# 3V3.net
KiCad netlist of a schematic drawn in Altium Designer
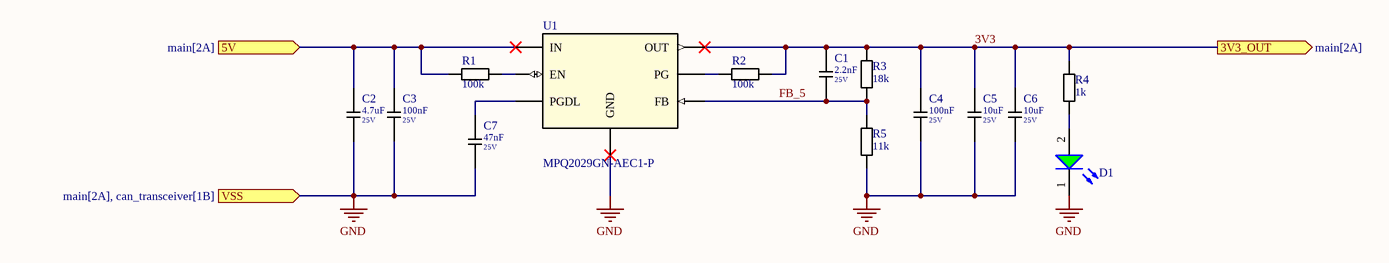
[diagram p0: 3V3.SchDoc]

(export (version "E")
  (design (tool "Eeschema 10.0.6"))
  (components
    (comp (ref "C1")
      (value "2.2nF")
      (footprint "0603_C")
      (description "Keramikkondensatoren 0603")
      (fields (field (name "SPG") "25V") (field (name "Comment") "2.2nF_25V"))
      (libsource (lib "Allgemeine_ETI_Schematic_Lib") (part "C_0603_Keramik"))
    )
    (comp (ref "C2")
      (value "4.7uF")
      (footprint "0603_C")
      (description "Keramikkondensatoren 0603")
      (fields (field (name "SPG") "25V") (field (name "Comment") "4.7uF_25V"))
      (libsource (lib "Allgemeine_ETI_Schematic_Lib") (part "C_0603_Keramik"))
    )
    (comp (ref "C3")
      (value "100nF")
      (footprint "0603_C")
      (description "Keramikkondensatoren 0603")
      (fields (field (name "SPG") "25V") (field (name "Comment") "100nF_25V"))
      (libsource (lib "Allgemeine_ETI_Schematic_Lib") (part "C_0603_Keramik"))
    )
    (comp (ref "C4")
      (value "100nF")
      (footprint "0603_C")
      (description "Keramikkondensatoren 0603")
      (fields (field (name "SPG") "25V") (field (name "Comment") "100nF_25V"))
      (libsource (lib "Allgemeine_ETI_Schematic_Lib") (part "C_0603_Keramik"))
    )
    (comp (ref "C5")
      (value "10uF")
      (footprint "0603_C")
      (description "Keramikkondensatoren 0603")
      (fields (field (name "SPG") "25V") (field (name "Comment") "10uF_25V"))
      (libsource (lib "Allgemeine_ETI_Schematic_Lib") (part "C_0603_Keramik"))
    )
    (comp (ref "C6")
      (value "10uF")
      (footprint "0603_C")
      (description "Keramikkondensatoren 0603")
      (fields (field (name "SPG") "25V") (field (name "Comment") "10uF_25V"))
      (libsource (lib "Allgemeine_ETI_Schematic_Lib") (part "C_0603_Keramik"))
    )
    (comp (ref "C7")
      (value "47nF")
      (footprint "0603_C")
      (description "Keramikkondensatoren 0603")
      (fields (field (name "SPG") "25V") (field (name "Comment") "47nF_25V"))
      (libsource (lib "Allgemeine_ETI_Schematic_Lib") (part "C_0603_Keramik"))
    )
    (comp (ref "D1")
      (value "Green, 3.2V, 140°")
      (footprint "WL-SMCD_0603")
      (description "WL-SMCD Mono-color Chip LED Diffused, SMT, size 0603, Green, 3.2V, 140°")
      (fields
        (field (name "MANUFACTURER PART NUMBER") "150060GS55040")
        (field (name "MANUFACTURER") "Wurth Elektronik")
      )
      (libsource (lib "Altium_WL-SMCD (rev24a)") (part "150060GS55040"))
    )
    (comp (ref "R1")
      (value "100k")
      (footprint "0603_R")
      (description "R 0603, 75V, 0.1W")
      (libsource (lib "Allgemeine_ETI_Schematic_Lib") (part "R_0603"))
    )
    (comp (ref "R2")
      (value "100k")
      (footprint "0603_R")
      (description "R 0603, 75V, 0.1W")
      (libsource (lib "Allgemeine_ETI_Schematic_Lib") (part "R_0603"))
    )
    (comp (ref "R3")
      (value "18k")
      (footprint "0603_R")
      (description "R 0603, 75V, 0.1W")
      (libsource (lib "") (part "R_0603_1"))
    )
    (comp (ref "R4")
      (value "1k")
      (footprint "0603_R")
      (description "R 0603, 75V, 0.1W")
      (libsource (lib "") (part "R_0603_1"))
    )
    (comp (ref "R5")
      (value "11k")
      (footprint "0603_R")
      (description "R 0603, 75V, 0.1W")
      (libsource (lib "") (part "R_0603_1"))
    )
    (comp (ref "U1")
      (value "MPQ2029GN-AEC1-P")
      (footprint "SOIC8-EP_MPQ2029_MNP")
      (description "No Description Available")
      (libsource (lib "KARaceIng25") (part "MPQ2029GN-AEC1-P"))
    )
  )
  (nets
    (net (code "1") (name "/3V3") (class "Default")
      (node (ref "C1") (pin "1") (pinfunction "1_1") (pintype "passive"))
      (node (ref "C4") (pin "1") (pinfunction "1_1") (pintype "passive"))
      (node (ref "C5") (pin "1") (pinfunction "1_1") (pintype "passive"))
      (node (ref "C6") (pin "1") (pinfunction "1_1") (pintype "passive"))
      (node (ref "R2") (pin "2") (pinfunction "2_2") (pintype "passive"))
      (node (ref "R3") (pin "2") (pinfunction "2_2") (pintype "passive"))
      (node (ref "R4") (pin "2") (pinfunction "2_2") (pintype "passive"))
      (node (ref "U1") (pin "1") (pinfunction "OUT_1") (pintype "output"))
    )
    (net (code "2") (name "/5V") (class "Default")
      (node (ref "C2") (pin "1") (pinfunction "1_1") (pintype "passive"))
      (node (ref "C3") (pin "1") (pinfunction "1_1") (pintype "passive"))
      (node (ref "R1") (pin "1") (pinfunction "1_1") (pintype "passive"))
      (node (ref "U1") (pin "4") (pinfunction "IN_4") (pintype "power_in"))
    )
    (net (code "3") (name "/FB_5") (class "Default")
      (node (ref "C1") (pin "2") (pinfunction "2_2") (pintype "passive"))
      (node (ref "R3") (pin "1") (pinfunction "1_1") (pintype "passive"))
      (node (ref "R5") (pin "2") (pinfunction "2_2") (pintype "passive"))
      (node (ref "U1") (pin "8") (pinfunction "FB_8") (pintype "input"))
    )
    (net (code "4") (name "GND") (class "Default")
      (node (ref "C2") (pin "2") (pinfunction "2_2") (pintype "passive"))
      (node (ref "C3") (pin "2") (pinfunction "2_2") (pintype "passive"))
      (node (ref "C4") (pin "2") (pinfunction "2_2") (pintype "passive"))
      (node (ref "C5") (pin "2") (pinfunction "2_2") (pintype "passive"))
      (node (ref "C6") (pin "2") (pinfunction "2_2") (pintype "passive"))
      (node (ref "C7") (pin "2") (pinfunction "2_2") (pintype "passive"))
      (node (ref "D1") (pin "1") (pinfunction "K_1") (pintype "passive"))
      (node (ref "R5") (pin "1") (pinfunction "1_1") (pintype "passive"))
      (node (ref "U1") (pin "3") (pinfunction "GND_3") (pintype "power_in"))
    )
    (net (code "5") (name "Net-(D1-A)") (class "Default")
      (node (ref "D1") (pin "2") (pinfunction "A_2") (pintype "passive"))
      (node (ref "R4") (pin "1") (pinfunction "1_1") (pintype "passive"))
    )
    (net (code "6") (name "Net-(U1-EN)") (class "Default")
      (node (ref "R1") (pin "2") (pinfunction "2_2") (pintype "passive"))
      (node (ref "U1") (pin "5") (pinfunction "EN_5") (pintype "bidirectional"))
    )
    (net (code "7") (name "Net-(U1-PG)") (class "Default")
      (node (ref "R2") (pin "1") (pinfunction "1_1") (pintype "passive"))
      (node (ref "U1") (pin "6") (pinfunction "PG_6") (pintype "passive"))
    )
    (net (code "8") (name "Net-(U1-PGDL)") (class "Default")
      (node (ref "C7") (pin "1") (pinfunction "1_1") (pintype "passive"))
      (node (ref "U1") (pin "7") (pinfunction "PGDL_7") (pintype "passive"))
    )
  )
)
